# ESP_Grow_Main_V2_1_CPU.net
KiCad netlist of a schematic drawn in Altium Designer
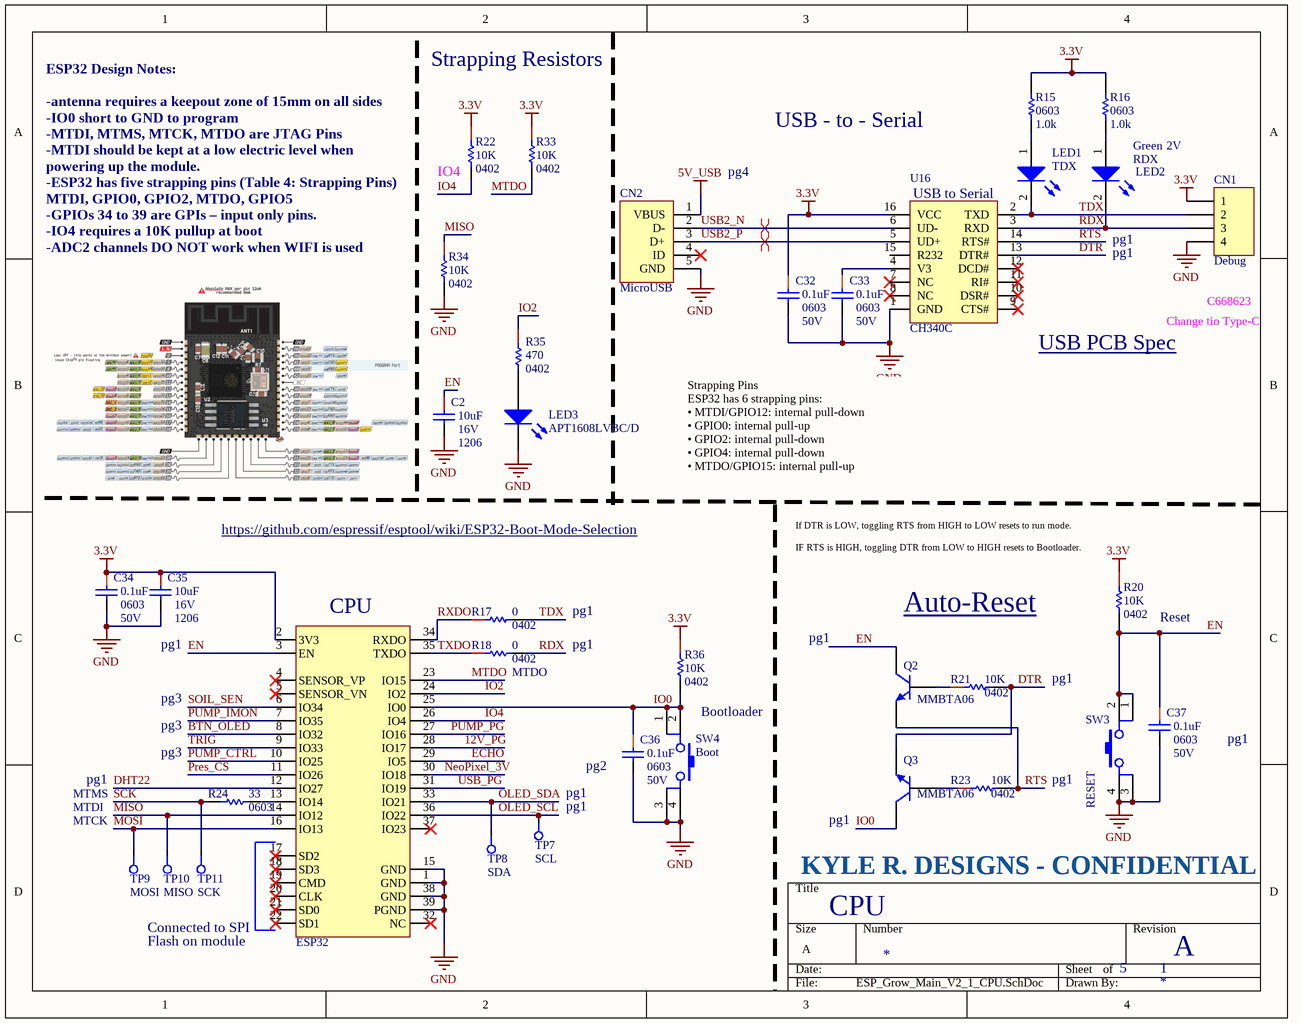
[diagram p0: ESP_Grow_Main_V2_1_CPU.SchDoc]

(export (version "E")
  (design (tool "Eeschema 10.0.6"))
  (components
    (comp (ref "C2")
      (value "10uF")
      (footprint "CAPC1206(3216)_M")
      (fields (field (name "VOLTAGE - RATED") "16V") (field (name "PACKAGE") "1206"))
      (libsource (lib "Kyle-Passive") (part "CAP CER 10UF 16V 1206"))
    )
    (comp (ref "C32")
      (value "0.1uF")
      (footprint "CAPC0603(1608)_L")
      (description "100NF 50V 0603")
      (fields
        (field (name "MANUFACTURER") "YAGEO")
        (field (name "MANUFACTURER PART NUMBER") "CC0603KRX7R9BB104")
        (field (name "CAPACITANCE") "0.1uF")
        (field (name "PACKAGE / CASE") "0603")
        (field (name "VOLTAGE - RATED") "50V")
      )
      (libsource (lib "JLCPCB_Capacitors") (part "0.1uF_0603"))
    )
    (comp (ref "C33")
      (value "0.1uF")
      (footprint "CAPC0603(1608)_L")
      (description "100NF 50V 0603")
      (fields
        (field (name "MANUFACTURER") "YAGEO")
        (field (name "MANUFACTURER PART NUMBER") "CC0603KRX7R9BB104")
        (field (name "CAPACITANCE") "0.1uF")
        (field (name "PACKAGE / CASE") "0603")
        (field (name "VOLTAGE - RATED") "50V")
      )
      (libsource (lib "JLCPCB_Capacitors") (part "0.1uF_0603"))
    )
    (comp (ref "C34")
      (value "0.1uF")
      (footprint "CAPC0603(1608)_L")
      (description "100NF 50V 0603")
      (fields
        (field (name "MANUFACTURER") "YAGEO")
        (field (name "MANUFACTURER PART NUMBER") "CC0603KRX7R9BB104")
        (field (name "CAPACITANCE") "0.1uF")
        (field (name "PACKAGE / CASE") "0603")
        (field (name "VOLTAGE - RATED") "50V")
      )
      (libsource (lib "JLCPCB_Capacitors") (part "0.1uF_0603"))
    )
    (comp (ref "C35")
      (value "10uF")
      (footprint "CAPC1206(3216)_M")
      (fields (field (name "VOLTAGE - RATED") "16V") (field (name "PACKAGE") "1206"))
      (libsource (lib "Kyle-Passive") (part "CAP CER 10UF 16V 1206"))
    )
    (comp (ref "C36")
      (value "0.1uF")
      (footprint "CAPC0603(1608)_L")
      (description "100NF 50V 0603")
      (fields
        (field (name "MANUFACTURER") "YAGEO")
        (field (name "MANUFACTURER PART NUMBER") "CC0603KRX7R9BB104")
        (field (name "CAPACITANCE") "0.1uF")
        (field (name "PACKAGE / CASE") "0603")
        (field (name "VOLTAGE - RATED") "50V")
      )
      (libsource (lib "JLCPCB_Capacitors") (part "0.1uF_0603"))
    )
    (comp (ref "C37")
      (value "0.1uF")
      (footprint "CAPC0603(1608)_L")
      (description "100NF 50V 0603")
      (fields
        (field (name "MANUFACTURER") "YAGEO")
        (field (name "MANUFACTURER PART NUMBER") "CC0603KRX7R9BB104")
        (field (name "CAPACITANCE") "0.1uF")
        (field (name "PACKAGE / CASE") "0603")
        (field (name "VOLTAGE - RATED") "50V")
      )
      (libsource (lib "JLCPCB_Capacitors") (part "0.1uF_0603"))
    )
    (comp (ref "CN1")
      (value "Debug")
      (footprint "HDR1X4")
      (description "Header, 4-Pin")
      (fields
        (field (name "MANUFACTURER") "Sullins Connector Solutions")
        (field (name "MANUFACTURER PART NUMBER") "PRPC004SAAN-RC")
      )
      (libsource (lib "Kyle-Connectors") (part "Header 4"))
    )
    (comp (ref "CN2")
      (value "MicroUSB")
      (footprint "10118194-0001LF")
      (description "Amphenol FCI CONN USB MICRO B RECPT SMT R/A")
      (fields
        (field (name "MANUFACTURER") "Amphenol FCI")
        (field (name "MANUFACTURER PART NUMBER") "10118194-0001LF")
      )
      (libsource (lib "OLogic-Connectors") (part "10118194-0001LF"))
    )
    (comp (ref "LED1")
      (value "TDX")
      (footprint "SM-LED-0603")
      (description "LED GREEN CLEAR THIN 0603 SMD")
      (fields
        (field (name "MANUFACTURER PART NUMBER") "LTST-C191KGKT")
        (field (name "MANUFACTURER") "Lite-On Inc")
      )
      (libsource (lib "OLogic Nexus Vault") (part "OL_LED"))
    )
    (comp (ref "LED2")
      (value "RDX")
      (footprint "SM-LED-0603")
      (description "LED GREEN CLEAR THIN 0603 SMD")
      (fields
        (field (name "MANUFACTURER PART NUMBER") "LTST-C191KGKT")
        (field (name "COLOR") "Green")
        (field (name "MANUFACTURER") "Lite-On Inc")
        (field (name "VOLTAGE - FORWARD (VF) (TYP)") "2V")
      )
      (libsource (lib "OLogic Nexus Vault") (part "OL_LED"))
    )
    (comp (ref "LED3")
      (value "APT1608LVBC/D")
      (footprint "SM-LED-0603")
      (description "LED BLUE CLEAR 2SMD 2.65V")
      (libsource (lib "OLogic Nexus Vault") (part "Blue"))
    )
    (comp (ref "Q2")
      (value "MMBTA06")
      (footprint "SOT23")
      (description "TRANS NPN 80V 0.5A SOT-23")
      (fields
        (field (name "MANUFACTURER") "ON Semiconductor")
        (field (name "MANUFACTURER PART NUMBER") "MMBTA06LT3G")
      )
      (libsource (lib "OLogic-Trans-Drivers") (part "MMBTA06"))
    )
    (comp (ref "Q3")
      (value "MMBTA06")
      (footprint "SOT23")
      (description "TRANS NPN 80V 0.5A SOT-23")
      (fields
        (field (name "MANUFACTURER") "ON Semiconductor")
        (field (name "MANUFACTURER PART NUMBER") "MMBTA06LT3G")
      )
      (libsource (lib "OLogic-Trans-Drivers") (part "MMBTA06"))
    )
    (comp (ref "R15")
      (value "1.0K")
      (footprint "RESC0603(1608)_N")
      (description "1.0K 0603")
      (fields
        (field (name "MANUFACTURER") "Stackpole Electronics Inc.")
        (field (name "MANUFACTURER PART NUMBER") "RMCF0603FT1K00")
        (field (name "PACKAGE / CASE") "0603")
        (field (name "RESISTANCE (OHMS)") "1.0k")
      )
      (libsource (lib "Kyle-Passive") (part "RES 1K OHM 1% 1/10W 0603"))
    )
    (comp (ref "R16")
      (value "1.0K")
      (footprint "RESC0603(1608)_N")
      (description "1.0K 0603")
      (fields
        (field (name "MANUFACTURER") "Stackpole Electronics Inc.")
        (field (name "MANUFACTURER PART NUMBER") "RMCF0603FT1K00")
        (field (name "PACKAGE / CASE") "0603")
        (field (name "RESISTANCE (OHMS)") "1.0k")
      )
      (libsource (lib "Kyle-Passive") (part "RES 1K OHM 1% 1/10W 0603"))
    )
    (comp (ref "R17")
      (value "0.0")
      (footprint "RESC0402(1005)_M")
      (description "RES 0.0 OHM JUMPER 1/10W 0402")
      (fields
        (field (name "PACKAGE (IMPERIAL)") "0402")
        (field (name "POWER") "63mW")
        (field (name "TOLERANCE") "0%")
        (field (name "RESISTANCE") "0")
      )
      (libsource (lib "OLogic Nexus Vault") (part "=Resistance"))
    )
    (comp (ref "R18")
      (value "0.0")
      (footprint "RESC0402(1005)_M")
      (description "RES 0.0 OHM JUMPER 1/10W 0402")
      (fields
        (field (name "PACKAGE (IMPERIAL)") "0402")
        (field (name "POWER") "63mW")
        (field (name "TOLERANCE") "0%")
        (field (name "RESISTANCE") "0")
      )
      (libsource (lib "OLogic Nexus Vault") (part "=Resistance"))
    )
    (comp (ref "R20")
      (value "0402WGF1002TCE")
      (footprint "RESC0402(1005)_N")
      (description "10KOHMS ±1% 1/10W 0402")
      (fields (field (name "RESISTANCE") "10K") (field (name "PACKAGE") "0402"))
      (libsource (lib "JLCPCB_Resistors") (part "10k_0402"))
    )
    (comp (ref "R21")
      (value "0402WGF1002TCE")
      (footprint "RESC0402(1005)_N")
      (description "10KOHMS ±1% 1/10W 0402")
      (fields (field (name "RESISTANCE") "10K") (field (name "PACKAGE") "0402"))
      (libsource (lib "JLCPCB_Resistors") (part "10k_0402"))
    )
    (comp (ref "R22")
      (value "0402WGF1002TCE")
      (footprint "RESC0402(1005)_N")
      (description "10KOHMS ±1% 1/10W 0402")
      (fields (field (name "RESISTANCE") "10K") (field (name "PACKAGE") "0402"))
      (libsource (lib "JLCPCB_Resistors") (part "10k_0402"))
    )
    (comp (ref "R23")
      (value "0402WGF1002TCE")
      (footprint "RESC0402(1005)_N")
      (description "10KOHMS ±1% 1/10W 0402")
      (fields (field (name "RESISTANCE") "10K") (field (name "PACKAGE") "0402"))
      (libsource (lib "JLCPCB_Resistors") (part "10k_0402"))
    )
    (comp (ref "R24")
      (value "33")
      (footprint "RESC0603(1608)_L")
      (description "33 0603")
      (fields
        (field (name "MANUFACTURER") "Panasonic Electronic Components")
        (field (name "MANUFACTURER PART NUMBER") "ERJ-3GEYJ330V")
        (field (name "RESISTANCE (OHMS)") "33")
        (field (name "PACKAGE / CASE") "0603")
      )
      (libsource (lib "OLogic-Passive") (part "RES 33 OHM 1/10W 5% 0603 SMD"))
    )
    (comp (ref "R33")
      (value "0402WGF1002TCE")
      (footprint "RESC0402(1005)_N")
      (description "10KOHMS ±1% 1/10W 0402")
      (fields (field (name "RESISTANCE") "10K") (field (name "PACKAGE") "0402"))
      (libsource (lib "JLCPCB_Resistors") (part "10k_0402"))
    )
    (comp (ref "R34")
      (value "0402WGF1002TCE")
      (footprint "RESC0402(1005)_N")
      (description "10KOHMS ±1% 1/10W 0402")
      (fields (field (name "RESISTANCE") "10K") (field (name "PACKAGE") "0402"))
      (libsource (lib "JLCPCB_Resistors") (part "10k_0402"))
    )
    (comp (ref "R35")
      (value "470")
      (footprint "RESC0402(1005)_M")
      (description "RES 470 OHM 1% 1/10W 0402")
      (fields
        (field (name "PACKAGE (IMPERIAL)") "0402")
        (field (name "POWER") "63mW")
        (field (name "TOLERANCE") "1%")
        (field (name "RESISTANCE") "470")
      )
      (libsource (lib "OLogic Nexus Vault") (part "=Resistance"))
    )
    (comp (ref "R36")
      (value "0402WGF1002TCE")
      (footprint "RESC0402(1005)_N")
      (description "10KOHMS ±1% 1/10W 0402")
      (fields (field (name "RESISTANCE") "10K") (field (name "PACKAGE") "0402"))
      (libsource (lib "JLCPCB_Resistors") (part "10k_0402"))
    )
    (comp (ref "SW3")
      (value "RESET")
      (footprint "SW TACT Red 6mm x 6mm")
      (description "SWITCH TACTILE SPST-NO 0.05A 12V")
      (fields
        (field (name "MANUFACTURER") "C&K")
        (field (name "MANUFACTURER PART NUMBER") "PTS645SM43SMTR92 LFS")
      )
      (libsource (lib "OLogic-Switches") (part "PTS645SM43SMTR92 LFS"))
    )
    (comp (ref "SW4")
      (value "Boot")
      (footprint "SW TACT Red 6mm x 6mm")
      (description "SWITCH TACTILE SPST-NO 0.05A 12V")
      (fields
        (field (name "MANUFACTURER") "C&K")
        (field (name "MANUFACTURER PART NUMBER") "PTS645SM43SMTR92 LFS")
      )
      (libsource (lib "OLogic-Switches") (part "PTS645SM43SMTR92 LFS"))
    )
    (comp (ref "TP7")
      (value "SCL")
      (footprint "Pogo-Testpoint")
      (description "Test Point- Current one")
      (libsource (lib "OLogic Nexus Vault") (part "TestPoint"))
    )
    (comp (ref "TP8")
      (value "SDA")
      (footprint "Pogo-Testpoint")
      (description "Test Point- Current one")
      (libsource (lib "OLogic Nexus Vault") (part "TestPoint"))
    )
    (comp (ref "TP9")
      (value "MOSI")
      (footprint "Pogo-Testpoint")
      (description "Test Point- Current one")
      (libsource (lib "OLogic Nexus Vault") (part "TestPoint"))
    )
    (comp (ref "TP10")
      (value "MISO")
      (footprint "Pogo-Testpoint")
      (description "Test Point- Current one")
      (libsource (lib "OLogic Nexus Vault") (part "TestPoint"))
    )
    (comp (ref "TP11")
      (value "SCK")
      (footprint "Pogo-Testpoint")
      (description "Test Point- Current one")
      (libsource (lib "OLogic Nexus Vault") (part "TestPoint"))
    )
    (comp (ref "U16")
      (value "CH340C")
      (footprint "SOP-16")
      (description "USB to Serial UART")
      (libsource (lib "Kyle_Lib_04-20-19") (part "CH340C"))
    )
    (comp (ref "U17")
      (value "ESP32")
      (footprint "ESP32")
      (description "ESP32 module")
      (libsource (lib "Kyle_Lib_04-20-19") (part "U/ESP32-WROOM-32D"))
    )
  )
  (nets
    (net (code "1") (name "/12V_PG") (class "Default")
      (node (ref "U17") (pin "28") (pinfunction "IO17_28") (pintype "passive"))
    )
    (net (code "2") (name "/BTN_OLED") (class "Default")
      (node (ref "U17") (pin "8") (pinfunction "IO32_8") (pintype "passive"))
    )
    (net (code "3") (name "/DHT22") (class "Default")
      (node (ref "U17") (pin "12") (pinfunction "IO27_12") (pintype "passive"))
    )
    (net (code "4") (name "/DTR") (class "Default")
      (node (ref "Q3") (pin "2") (pinfunction "E_2") (pintype "passive"))
      (node (ref "R21") (pin "2") (pinfunction "2_2") (pintype "passive"))
      (node (ref "U16") (pin "13") (pinfunction "DTR#_13") (pintype "power_in"))
    )
    (net (code "5") (name "/ECHO") (class "Default")
      (node (ref "U17") (pin "29") (pinfunction "IO5_29") (pintype "passive"))
    )
    (net (code "6") (name "/EN") (class "Default")
      (node (ref "C2") (pin "1") (pinfunction "1_1") (pintype "passive"))
      (node (ref "C37") (pin "1") (pinfunction "1_1") (pintype "passive"))
      (node (ref "Q2") (pin "3") (pinfunction "C_3") (pintype "passive"))
      (node (ref "R20") (pin "2") (pinfunction "2_2") (pintype "passive"))
      (node (ref "SW3") (pin "1") (pinfunction "1_1") (pintype "passive"))
      (node (ref "SW3") (pin "2") (pinfunction "2_2") (pintype "passive"))
      (node (ref "U17") (pin "3") (pinfunction "EN_3") (pintype "passive"))
    )
    (net (code "7") (name "/IO0") (class "Default")
      (node (ref "C36") (pin "1") (pinfunction "1_1") (pintype "passive"))
      (node (ref "Q3") (pin "3") (pinfunction "C_3") (pintype "passive"))
      (node (ref "R36") (pin "2") (pinfunction "2_2") (pintype "passive"))
      (node (ref "SW4") (pin "1") (pinfunction "1_1") (pintype "passive"))
      (node (ref "SW4") (pin "2") (pinfunction "2_2") (pintype "passive"))
      (node (ref "U17") (pin "25") (pinfunction "IO0_25") (pintype "passive"))
    )
    (net (code "8") (name "/IO2") (class "Default")
      (node (ref "R35") (pin "1") (pinfunction "1_1") (pintype "passive"))
      (node (ref "U17") (pin "24") (pinfunction "IO2_24") (pintype "passive"))
    )
    (net (code "9") (name "/IO4") (class "Default")
      (node (ref "R22") (pin "2") (pinfunction "2_2") (pintype "passive"))
      (node (ref "U17") (pin "26") (pinfunction "IO4_26") (pintype "passive"))
    )
    (net (code "10") (name "/MISO") (class "Default")
      (node (ref "R34") (pin "1") (pinfunction "1_1") (pintype "passive"))
      (node (ref "TP10") (pin "1") (pinfunction "1_1") (pintype "passive"))
      (node (ref "U17") (pin "14") (pinfunction "IO12_14") (pintype "passive"))
    )
    (net (code "11") (name "/MOSI") (class "Default")
      (node (ref "TP9") (pin "1") (pinfunction "1_1") (pintype "passive"))
      (node (ref "U17") (pin "16") (pinfunction "IO13_16") (pintype "passive"))
    )
    (net (code "12") (name "/MTDO") (class "Default")
      (node (ref "R33") (pin "2") (pinfunction "2_2") (pintype "passive"))
      (node (ref "U17") (pin "23") (pinfunction "IO15_23") (pintype "passive"))
    )
    (net (code "13") (name "/NeoPixel_3V") (class "Default")
      (node (ref "U17") (pin "30") (pinfunction "IO18_30") (pintype "passive"))
    )
    (net (code "14") (name "/OLED_SCL") (class "Default")
      (node (ref "TP7") (pin "1") (pinfunction "1_1") (pintype "passive"))
      (node (ref "U17") (pin "36") (pinfunction "IO22_36") (pintype "passive"))
    )
    (net (code "15") (name "/OLED_SDA") (class "Default")
      (node (ref "TP8") (pin "1") (pinfunction "1_1") (pintype "passive"))
      (node (ref "U17") (pin "33") (pinfunction "IO21_33") (pintype "passive"))
    )
    (net (code "16") (name "/PUMP_CTRL") (class "Default")
      (node (ref "U17") (pin "10") (pinfunction "IO25_10") (pintype "passive"))
    )
    (net (code "17") (name "/PUMP_IMON") (class "Default")
      (node (ref "U17") (pin "7") (pinfunction "IO35_7") (pintype "passive"))
    )
    (net (code "18") (name "/PUMP_PG") (class "Default")
      (node (ref "U17") (pin "27") (pinfunction "IO16_27") (pintype "passive"))
    )
    (net (code "19") (name "/Pres_CS") (class "Default")
      (node (ref "U17") (pin "11") (pinfunction "IO26_11") (pintype "passive"))
    )
    (net (code "20") (name "/RDX") (class "Default")
      (node (ref "CN1") (pin "3") (pinfunction "3_3") (pintype "passive"))
      (node (ref "LED2") (pin "2") (pinfunction "K_2") (pintype "passive"))
      (node (ref "R18") (pin "2") (pinfunction "2_2") (pintype "passive"))
      (node (ref "U16") (pin "3") (pinfunction "RXD_3") (pintype "power_in"))
    )
    (net (code "21") (name "/RTS") (class "Default")
      (node (ref "Q2") (pin "2") (pinfunction "E_2") (pintype "passive"))
      (node (ref "R23") (pin "2") (pinfunction "2_2") (pintype "passive"))
      (node (ref "U16") (pin "14") (pinfunction "RTS#_14") (pintype "power_in"))
    )
    (net (code "22") (name "/RXDO") (class "Default")
      (node (ref "R17") (pin "1") (pinfunction "1_1") (pintype "passive"))
      (node (ref "U17") (pin "34") (pinfunction "RXDO_34") (pintype "passive"))
    )
    (net (code "23") (name "/SCK") (class "Default")
      (node (ref "R24") (pin "2") (pinfunction "2_2") (pintype "passive"))
      (node (ref "TP11") (pin "1") (pinfunction "1_1") (pintype "passive"))
    )
    (net (code "24") (name "/SOIL_SEN") (class "Default")
      (node (ref "U17") (pin "6") (pinfunction "IO34_6") (pintype "passive"))
    )
    (net (code "25") (name "/TDX") (class "Default")
      (node (ref "CN1") (pin "2") (pinfunction "2_2") (pintype "passive"))
      (node (ref "LED1") (pin "2") (pinfunction "K_2") (pintype "passive"))
      (node (ref "R17") (pin "2") (pinfunction "2_2") (pintype "passive"))
      (node (ref "U16") (pin "2") (pinfunction "TXD_2") (pintype "power_in"))
    )
    (net (code "26") (name "/TRIG") (class "Default")
      (node (ref "U17") (pin "9") (pinfunction "IO33_9") (pintype "passive"))
    )
    (net (code "27") (name "/TXDO") (class "Default")
      (node (ref "R18") (pin "1") (pinfunction "1_1") (pintype "passive"))
      (node (ref "U17") (pin "35") (pinfunction "TXDO_35") (pintype "passive"))
    )
    (net (code "28") (name "/USB2_N") (class "Default")
      (node (ref "CN2") (pin "2") (pinfunction "D-_2") (pintype "passive"))
      (node (ref "U16") (pin "6") (pinfunction "UD-_6") (pintype "power_in"))
    )
    (net (code "29") (name "/USB2_P") (class "Default")
      (node (ref "CN2") (pin "3") (pinfunction "D+_3") (pintype "passive"))
      (node (ref "U16") (pin "5") (pinfunction "UD+_5") (pintype "power_in"))
    )
    (net (code "30") (name "/USB_PG") (class "Default")
      (node (ref "U17") (pin "31") (pinfunction "IO19_31") (pintype "passive"))
    )
    (net (code "31") (name "3.3V") (class "Default")
      (node (ref "C32") (pin "1") (pinfunction "1_1") (pintype "passive"))
      (node (ref "C34") (pin "1") (pinfunction "1_1") (pintype "passive"))
      (node (ref "C35") (pin "1") (pinfunction "1_1") (pintype "passive"))
      (node (ref "CN1") (pin "1") (pinfunction "1_1") (pintype "passive"))
      (node (ref "R15") (pin "2") (pinfunction "2_2") (pintype "passive"))
      (node (ref "R16") (pin "2") (pinfunction "2_2") (pintype "passive"))
      (node (ref "R20") (pin "1") (pinfunction "1_1") (pintype "passive"))
      (node (ref "R22") (pin "1") (pinfunction "1_1") (pintype "passive"))
      (node (ref "R33") (pin "1") (pinfunction "1_1") (pintype "passive"))
      (node (ref "R36") (pin "1") (pinfunction "1_1") (pintype "passive"))
      (node (ref "U16") (pin "16") (pinfunction "VCC_16") (pintype "power_in"))
      (node (ref "U17") (pin "2") (pinfunction "3V3_2") (pintype "power_in"))
    )
    (net (code "32") (name "5V_USB") (class "Default")
      (node (ref "CN2") (pin "1") (pinfunction "VBUS_1") (pintype "power_in"))
    )
    (net (code "33") (name "GND") (class "Default")
      (node (ref "C2") (pin "2") (pinfunction "2_2") (pintype "passive"))
      (node (ref "C32") (pin "2") (pinfunction "2_2") (pintype "passive"))
      (node (ref "C33") (pin "2") (pinfunction "2_2") (pintype "passive"))
      (node (ref "C34") (pin "2") (pinfunction "2_2") (pintype "passive"))
      (node (ref "C35") (pin "2") (pinfunction "2_2") (pintype "passive"))
      (node (ref "C36") (pin "2") (pinfunction "2_2") (pintype "passive"))
      (node (ref "C37") (pin "2") (pinfunction "2_2") (pintype "passive"))
      (node (ref "CN1") (pin "4") (pinfunction "4_4") (pintype "passive"))
      (node (ref "CN2") (pin "5") (pinfunction "GND_5") (pintype "power_in"))
      (node (ref "LED3") (pin "2") (pinfunction "Cathode_2") (pintype "passive"))
      (node (ref "R34") (pin "2") (pinfunction "2_2") (pintype "passive"))
      (node (ref "SW3") (pin "3") (pinfunction "3_3") (pintype "passive"))
      (node (ref "SW3") (pin "4") (pinfunction "4_4") (pintype "passive"))
      (node (ref "SW4") (pin "3") (pinfunction "3_3") (pintype "passive"))
      (node (ref "SW4") (pin "4") (pinfunction "4_4") (pintype "passive"))
      (node (ref "U16") (pin "1") (pinfunction "GND_1") (pintype "power_in"))
      (node (ref "U17") (pin "1") (pinfunction "GND_1") (pintype "power_in"))
      (node (ref "U17") (pin "15") (pinfunction "GND_15") (pintype "passive"))
      (node (ref "U17") (pin "38") (pinfunction "GND_38") (pintype "power_in"))
      (node (ref "U17") (pin "39") (pinfunction "PGND_39") (pintype "power_in"))
    )
    (net (code "34") (name "Net-(LED1-A)") (class "Default")
      (node (ref "LED1") (pin "1") (pinfunction "A_1") (pintype "passive"))
      (node (ref "R15") (pin "1") (pinfunction "1_1") (pintype "passive"))
    )
    (net (code "35") (name "Net-(LED2-A)") (class "Default")
      (node (ref "LED2") (pin "1") (pinfunction "A_1") (pintype "passive"))
      (node (ref "R16") (pin "1") (pinfunction "1_1") (pintype "passive"))
    )
    (net (code "36") (name "Net-(LED3-Anode)") (class "Default")
      (node (ref "LED3") (pin "1") (pinfunction "Anode_1") (pintype "passive"))
      (node (ref "R35") (pin "2") (pinfunction "2_2") (pintype "passive"))
    )
    (net (code "37") (name "Net-(Q2-B)") (class "Default")
      (node (ref "Q2") (pin "1") (pinfunction "B_1") (pintype "passive"))
      (node (ref "R21") (pin "1") (pinfunction "1_1") (pintype "passive"))
    )
    (net (code "38") (name "Net-(Q3-B)") (class "Default")
      (node (ref "Q3") (pin "1") (pinfunction "B_1") (pintype "passive"))
      (node (ref "R23") (pin "1") (pinfunction "1_1") (pintype "passive"))
    )
    (net (code "39") (name "Net-(U16-V3)") (class "Default")
      (node (ref "C33") (pin "1") (pinfunction "1_1") (pintype "passive"))
      (node (ref "U16") (pin "4") (pinfunction "V3_4") (pintype "power_in"))
    )
    (net (code "40") (name "Net-(U17-IO14)") (class "Default")
      (node (ref "R24") (pin "1") (pinfunction "1_1") (pintype "passive"))
      (node (ref "U17") (pin "13") (pinfunction "IO14_13") (pintype "passive"))
    )
    (net (code "41") (name "unconnected-(CN2-ID-Pad4)") (class "Default")
      (node (ref "CN2") (pin "4") (pinfunction "ID_4") (pintype "passive+no_connect"))
    )
    (net (code "42") (name "unconnected-(U16-CTS#-Pad9)") (class "Default")
      (node (ref "U16") (pin "9") (pinfunction "CTS#_9") (pintype "power_in+no_connect"))
    )
    (net (code "43") (name "unconnected-(U16-DCD#-Pad12)") (class "Default")
      (node (ref "U16") (pin "12") (pinfunction "DCD#_12") (pintype "power_in+no_connect"))
    )
    (net (code "44") (name "unconnected-(U16-DSR#-Pad10)") (class "Default")
      (node (ref "U16") (pin "10") (pinfunction "DSR#_10") (pintype "power_in+no_connect"))
    )
    (net (code "45") (name "unconnected-(U16-NC-Pad7)") (class "Default")
      (node (ref "U16") (pin "7") (pinfunction "NC_7") (pintype "power_in+no_connect"))
    )
    (net (code "46") (name "unconnected-(U16-NC-Pad8)") (class "Default")
      (node (ref "U16") (pin "8") (pinfunction "NC_8") (pintype "power_in+no_connect"))
    )
    (net (code "47") (name "unconnected-(U16-R232-Pad15)") (class "Default")
      (node (ref "U16") (pin "15") (pinfunction "R232_15") (pintype "power_in"))
    )
    (net (code "48") (name "unconnected-(U16-RI#-Pad11)") (class "Default")
      (node (ref "U16") (pin "11") (pinfunction "RI#_11") (pintype "power_in+no_connect"))
    )
    (net (code "49") (name "unconnected-(U17-CLK-Pad20)") (class "Default")
      (node (ref "U17") (pin "20") (pinfunction "CLK_20") (pintype "passive+no_connect"))
    )
    (net (code "50") (name "unconnected-(U17-CMD-Pad19)") (class "Default")
      (node (ref "U17") (pin "19") (pinfunction "CMD_19") (pintype "passive+no_connect"))
    )
    (net (code "51") (name "unconnected-(U17-IO23-Pad37)") (class "Default")
      (node (ref "U17") (pin "37") (pinfunction "IO23_37") (pintype "passive+no_connect"))
    )
    (net (code "52") (name "unconnected-(U17-NC-Pad32)") (class "Default")
      (node (ref "U17") (pin "32") (pinfunction "NC_32") (pintype "passive+no_connect"))
    )
    (net (code "53") (name "unconnected-(U17-SD0-Pad21)") (class "Default")
      (node (ref "U17") (pin "21") (pinfunction "SD0_21") (pintype "passive+no_connect"))
    )
    (net (code "54") (name "unconnected-(U17-SD1-Pad22)") (class "Default")
      (node (ref "U17") (pin "22") (pinfunction "SD1_22") (pintype "passive+no_connect"))
    )
    (net (code "55") (name "unconnected-(U17-SD2-Pad17)") (class "Default")
      (node (ref "U17") (pin "17") (pinfunction "SD2_17") (pintype "passive+no_connect"))
    )
    (net (code "56") (name "unconnected-(U17-SD3-Pad18)") (class "Default")
      (node (ref "U17") (pin "18") (pinfunction "SD3_18") (pintype "passive+no_connect"))
    )
    (net (code "57") (name "unconnected-(U17-SENSOR_VN-Pad5)") (class "Default")
      (node (ref "U17") (pin "5") (pinfunction "SENSOR_VN_5") (pintype "passive+no_connect"))
    )
    (net (code "58") (name "unconnected-(U17-SENSOR_VP-Pad4)") (class "Default")
      (node (ref "U17") (pin "4") (pinfunction "SENSOR_VP_4") (pintype "passive+no_connect"))
    )
  )
)
